# FD_Capacitance_Sensor_v07.net
KiCad netlist of a schematic drawn in EAGLE
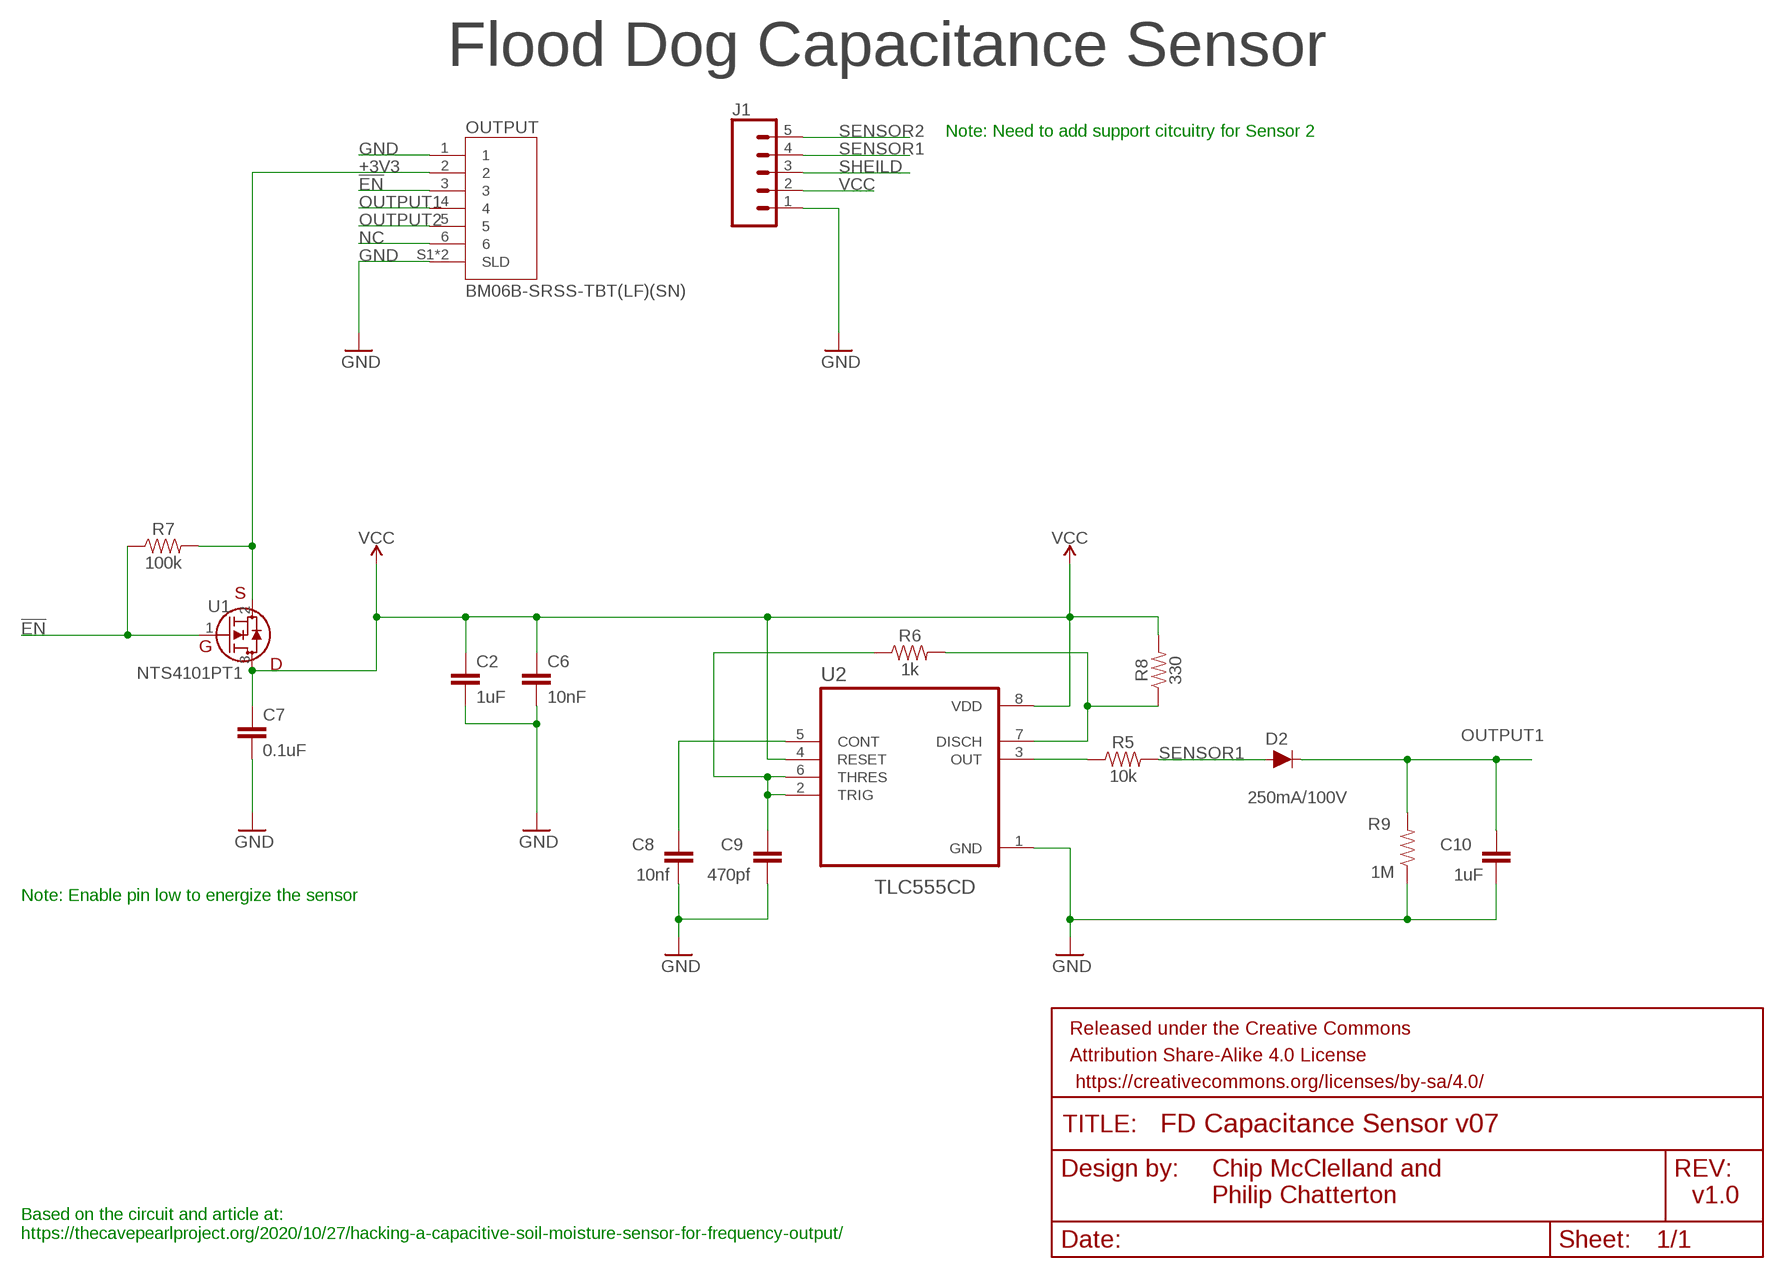
[diagram p0: schematic, sheet 1]

(export (version "E")
  (design (tool "Eeschema 10.0.6"))
  (components
    (comp (ref "C2")
      (value "1uF")
      (footprint "eagle-import:0805@1")
      (fields (field (name "HOUSEPART") "yes") (field (name "MPN") "MF-CAP-0805-1uF"))
      (libsource (lib "eagle-import") (part "CAP-MF-1UF-0805"))
    )
    (comp (ref "C6")
      (value "10nF")
      (footprint "eagle-import:0805@1")
      (fields (field (name "HOUSEPART") "NO") (field (name "MPN") "C0805X103K1RAC3316"))
      (libsource (lib "eagle-import") (part "CAP-10NF-0805"))
    )
    (comp (ref "C7")
      (value "0.1uF")
      (footprint "eagle-import:0805@1")
      (fields (field (name "HOUSEPART") "YES") (field (name "MPN") "MF-CAP-0805-0.1uF"))
      (libsource (lib "eagle-import") (part "CAP-MF-0.1UF-0805"))
    )
    (comp (ref "C8")
      (value "10nf")
      (footprint "eagle-import:C0805")
      (libsource (lib "eagle-import") (part "C-EUC0805"))
    )
    (comp (ref "C9")
      (value "470pf")
      (footprint "eagle-import:C0805")
      (libsource (lib "eagle-import") (part "C-EUC0805"))
    )
    (comp (ref "C10")
      (value "1uF")
      (footprint "eagle-import:C0805")
      (libsource (lib "eagle-import") (part "C-EUC0805"))
    )
    (comp (ref "D2")
      (value "250mA/100V")
      (footprint "eagle-import:SOD-323")
      (fields (field (name "MPN") "BAS16HT1G"))
      (libsource (lib "eagle-import") (part "DIODE-BAS16J"))
    )
    (comp (ref "FRAME1")
      (value "FRAME-LETTERNO_PACKAGE")
      (footprint "eagle-import:DUMMY")
      (fields (field (name "DESIGNER") "Nobody"))
      (libsource (lib "eagle-import") (part "FRAME-LETTERNO_PACKAGE"))
    )
    (comp (ref "J1")
      (value "CONN_05SCREW")
      (footprint "eagle-import:SCREWTERMINAL-3.5MM-5")
      (libsource (lib "eagle-import") (part "CONN_05SCREW"))
    )
    (comp (ref "OUTPUT")
      (value "BM06B-SRSS-TBT(LF)(SN)")
      (footprint "eagle-import:JST_BM06B-SRSS-TB(LF)(SN)")
      (libsource (lib "eagle-import") (part "BM06B-SRSS-TBT(LF)(SN)"))
    )
    (comp (ref "R5")
      (value "10k")
      (footprint "eagle-import:0805")
      (fields (field (name "MPN") "MF-RES-0805-10K"))
      (libsource (lib "eagle-import") (part "RESISTOR-MF-10K-0805"))
    )
    (comp (ref "R6")
      (value "1k")
      (footprint "eagle-import:0805")
      (fields (field (name "HOUSEPART") "YES") (field (name "MPN") "MF-RES-0805-1K"))
      (libsource (lib "eagle-import") (part "RESISTOR-MF-1K-0805"))
    )
    (comp (ref "R7")
      (value "100k")
      (footprint "eagle-import:0805")
      (fields (field (name "MPN") "MF-RES-0805-100K") (field (name "MPN_1") "MF-RES-0805-100K"))
      (libsource (lib "eagle-import") (part "RESISTOR-MF-100K-0805"))
    )
    (comp (ref "R8")
      (value "330")
      (footprint "eagle-import:0805")
      (fields (field (name "HOUSEPART") "YES") (field (name "MPN") "MF-RES-0805-330"))
      (libsource (lib "eagle-import") (part "RESISTOR-MF-330-0805"))
    )
    (comp (ref "R9")
      (value "1M")
      (footprint "eagle-import:0805")
      (fields (field (name "HOUSEPART") "YES") (field (name "MPN") "MF-RES-0805-1K"))
      (libsource (lib "eagle-import") (part "RESISTOR-MF-1K-0805"))
    )
    (comp (ref "U1")
      (value "NTS4101PT1")
      (footprint "eagle-import:SOT_101PT1_ONS")
      (libsource (lib "eagle-import") (part "NTS4101PT1"))
    )
    (comp (ref "U2")
      (value "TLC555CD")
      (footprint "eagle-import:SOIC127P599X175-8N")
      (fields (field (name "DIGI-KEY_PART_NUMBER") "296-52992-ND") (field (name "MF") "Texas Instruments"))
      (libsource (lib "eagle-import") (part "TLC555CD"))
    )
  )
  (nets
    (net (code "1") (name "/+3V3") (class "Default")
      (node (ref "OUTPUT") (pin "2") (pinfunction "2_2") (pintype "passive"))
      (node (ref "R7") (pin "2") (pinfunction "2_2") (pintype "passive"))
      (node (ref "U1") (pin "2") (pinfunction "S_2") (pintype "passive"))
    )
    (net (code "2") (name "/NC") (class "Default")
      (node (ref "OUTPUT") (pin "6") (pinfunction "6_6") (pintype "passive"))
    )
    (net (code "3") (name "/OUTPUT1") (class "Default")
      (node (ref "C10") (pin "2") (pinfunction "2_2") (pintype "passive"))
      (node (ref "D2") (pin "C") (pinfunction "C_C") (pintype "passive"))
      (node (ref "OUTPUT") (pin "4") (pinfunction "4_4") (pintype "passive"))
      (node (ref "R9") (pin "2") (pinfunction "2_2") (pintype "passive"))
    )
    (net (code "4") (name "/OUTPUT2") (class "Default")
      (node (ref "OUTPUT") (pin "5") (pinfunction "5_5") (pintype "passive"))
    )
    (net (code "5") (name "/SENSOR1") (class "Default")
      (node (ref "D2") (pin "A") (pinfunction "A_A") (pintype "passive"))
      (node (ref "J1") (pin "4") (pinfunction "4_4") (pintype "passive"))
      (node (ref "R5") (pin "2") (pinfunction "2_2") (pintype "passive"))
    )
    (net (code "6") (name "/SENSOR2") (class "Default")
      (node (ref "J1") (pin "5") (pinfunction "5_5") (pintype "passive"))
    )
    (net (code "7") (name "/SHEILD") (class "Default")
      (node (ref "J1") (pin "3") (pinfunction "3_3") (pintype "passive"))
    )
    (net (code "8") (name "/~{EN}") (class "Default")
      (node (ref "OUTPUT") (pin "3") (pinfunction "3_3") (pintype "passive"))
      (node (ref "R7") (pin "1") (pinfunction "1_1") (pintype "passive"))
      (node (ref "U1") (pin "1") (pinfunction "G_1") (pintype "passive"))
    )
    (net (code "9") (name "GND") (class "Default")
      (node (ref "C10") (pin "1") (pinfunction "1_1") (pintype "passive"))
      (node (ref "C2") (pin "2") (pinfunction "2_2") (pintype "passive"))
      (node (ref "C6") (pin "2") (pinfunction "2_2") (pintype "passive"))
      (node (ref "C7") (pin "2") (pinfunction "2_2") (pintype "passive"))
      (node (ref "C8") (pin "1") (pinfunction "1_1") (pintype "passive"))
      (node (ref "C9") (pin "1") (pinfunction "1_1") (pintype "passive"))
      (node (ref "J1") (pin "1") (pinfunction "1_1") (pintype "passive"))
      (node (ref "OUTPUT") (pin "1") (pinfunction "1_1") (pintype "passive"))
      (node (ref "OUTPUT") (pin "S1") (pinfunction "SLD_S1") (pintype "passive"))
      (node (ref "OUTPUT") (pin "S2") (pinfunction "SLD_S2") (pintype "passive"))
      (node (ref "R9") (pin "1") (pinfunction "1_1") (pintype "passive"))
      (node (ref "U2") (pin "1") (pinfunction "GND_1") (pintype "power_in"))
    )
    (net (code "10") (name "Net-(U2-CONT)") (class "Default")
      (node (ref "C8") (pin "2") (pinfunction "2_2") (pintype "passive"))
      (node (ref "U2") (pin "5") (pinfunction "CONT_5") (pintype "input"))
    )
    (net (code "11") (name "Net-(U2-DISCH)") (class "Default")
      (node (ref "R6") (pin "2") (pinfunction "2_2") (pintype "passive"))
      (node (ref "R8") (pin "1") (pinfunction "1_1") (pintype "passive"))
      (node (ref "U2") (pin "7") (pinfunction "DISCH_7") (pintype "output"))
    )
    (net (code "12") (name "Net-(U2-OUT)") (class "Default")
      (node (ref "R5") (pin "1") (pinfunction "1_1") (pintype "passive"))
      (node (ref "U2") (pin "3") (pinfunction "OUT_3") (pintype "output"))
    )
    (net (code "13") (name "Net-(U2-THRES)") (class "Default")
      (node (ref "C9") (pin "2") (pinfunction "2_2") (pintype "passive"))
      (node (ref "R6") (pin "1") (pinfunction "1_1") (pintype "passive"))
      (node (ref "U2") (pin "2") (pinfunction "TRIG_2") (pintype "input"))
      (node (ref "U2") (pin "6") (pinfunction "THRES_6") (pintype "input"))
    )
    (net (code "14") (name "VCC") (class "Default")
      (node (ref "C2") (pin "1") (pinfunction "1_1") (pintype "passive"))
      (node (ref "C6") (pin "1") (pinfunction "1_1") (pintype "passive"))
      (node (ref "C7") (pin "1") (pinfunction "1_1") (pintype "passive"))
      (node (ref "J1") (pin "2") (pinfunction "2_2") (pintype "passive"))
      (node (ref "R8") (pin "2") (pinfunction "2_2") (pintype "passive"))
      (node (ref "U1") (pin "3") (pinfunction "D_3") (pintype "passive"))
      (node (ref "U2") (pin "4") (pinfunction "RESET_4") (pintype "input"))
      (node (ref "U2") (pin "8") (pinfunction "VDD_8") (pintype "power_in"))
    )
  )
)
